# MAX17502.net
KiCad netlist of a schematic drawn in Altium Designer
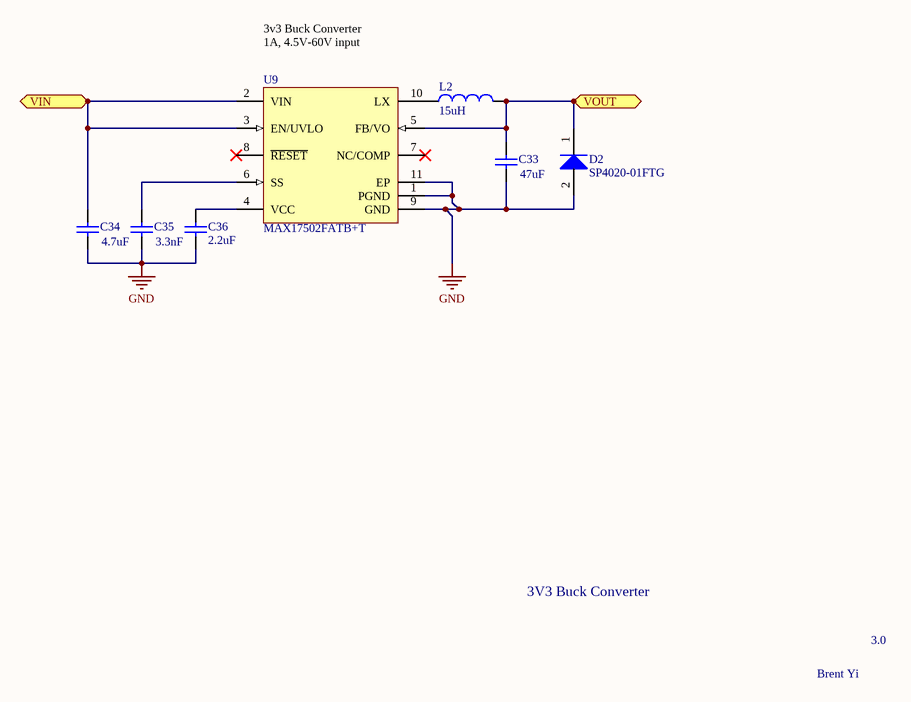
[diagram p0: MAX17502.SchDoc]

(export (version "E")
  (design (tool "Eeschema 10.0.6"))
  (components
    (comp (ref "C33")
      (value "47uF")
      (footprint "CAPC1210(3225)280_L")
      (description "CAP 100uF 10V Â±10% 1210 (3225 Metric) Thickness 2.8mm SMD")
      (fields (field (name "TOLERANCE") "Â±10%"))
      (libsource (lib "Altium Content Vault") (part "CMP-1038-02301-1"))
    )
    (comp (ref "C34")
      (value "4.7uF")
      (footprint "CAPC1210(3225)280_L")
      (description "CAP 100uF 10V Â±10% 1210 (3225 Metric) Thickness 2.8mm SMD")
      (fields (field (name "TOLERANCE") "Â±10%"))
      (libsource (lib "Altium Content Vault") (part "CMP-1038-02301-1"))
    )
    (comp (ref "C35")
      (value "3.3nF")
      (footprint "CAPC0603(1608)55_L")
      (description "CAP 2.2uF 16V Â±10% 0603 (1608 Metric) Thickness 0.55mm SMD")
      (fields (field (name "TOLERANCE") "Â±10%"))
      (libsource (lib "Altium Content Vault") (part "CMP-1035-02762-1"))
    )
    (comp (ref "C36")
      (value "2.2uF")
      (footprint "CAPC0603(1608)100_L")
      (description "CAP 1uF 6.3V Â±10% 0603 (1608 Metric) Thickness 1mm SMD")
      (fields (field (name "TOLERANCE") "Â±10%"))
      (libsource (lib "Altium Content Vault") (part "CMP-1035-02730-1"))
    )
    (comp (ref "D2")
      (value "SP4020-01FTG")
      (footprint "SOD323")
      (fields (field (name "PARTNUMBER") "MMSZ5262BT1G") (field (name "MANUFACTURER") "On Semiconductor"))
      (libsource (lib "Components") (part "SP4020-01FTG"))
    )
    (comp (ref "L2")
      (value "15uH")
      (footprint "SDR0604")
      (description "Inductor")
      (fields (field (name "Comment") "SDR0805-180ML") (field (name "PUBLISHER") "Altium Limited"))
      (libsource (lib "Components") (part "SDR0805-180ML"))
    )
    (comp (ref "U9")
      (value "MAX17502FATB+T")
      (footprint "MAXM-T1032N+1_V")
      (fields (field (name "MANUFACTURER") "Maxim"))
      (libsource (lib "Altium Content Vault") (part "MAXM-MAX17502-10"))
    )
  )
  (nets
    (net (code "1") (name "/VIN") (class "Default")
      (node (ref "C34") (pin "2") (pinfunction "2_2") (pintype "passive"))
      (node (ref "U9") (pin "2") (pinfunction "VIN_2") (pintype "power_in"))
      (node (ref "U9") (pin "3") (pinfunction "EN/UVLO_3") (pintype "input"))
    )
    (net (code "2") (name "/VOUT") (class "Default")
      (node (ref "C33") (pin "2") (pinfunction "2_2") (pintype "passive"))
      (node (ref "D2") (pin "1") (pinfunction "K_1") (pintype "passive"))
      (node (ref "L2") (pin "2") (pinfunction "2_2") (pintype "passive"))
      (node (ref "U9") (pin "5") (pinfunction "FB/VO_5") (pintype "input"))
    )
    (net (code "3") (name "GND") (class "Default")
      (node (ref "C33") (pin "1") (pinfunction "1_1") (pintype "passive"))
      (node (ref "C34") (pin "1") (pinfunction "1_1") (pintype "passive"))
      (node (ref "C35") (pin "2") (pinfunction "2_2") (pintype "passive"))
      (node (ref "C36") (pin "2") (pinfunction "2_2") (pintype "passive"))
      (node (ref "D2") (pin "2") (pinfunction "A_2") (pintype "passive"))
      (node (ref "U9") (pin "1") (pinfunction "PGND_1") (pintype "power_in"))
      (node (ref "U9") (pin "11") (pinfunction "EP_11") (pintype "power_in"))
      (node (ref "U9") (pin "9") (pinfunction "GND_9") (pintype "power_in"))
    )
    (net (code "4") (name "Net-(U9-LX)") (class "Default")
      (node (ref "L2") (pin "1") (pinfunction "1_1") (pintype "passive"))
      (node (ref "U9") (pin "10") (pinfunction "LX_10") (pintype "passive"))
    )
    (net (code "5") (name "Net-(U9-SS)") (class "Default")
      (node (ref "C35") (pin "1") (pinfunction "1_1") (pintype "passive"))
      (node (ref "U9") (pin "6") (pinfunction "SS_6") (pintype "input"))
    )
    (net (code "6") (name "Net-(U9-VCC)") (class "Default")
      (node (ref "C36") (pin "1") (pinfunction "1_1") (pintype "passive"))
      (node (ref "U9") (pin "4") (pinfunction "VCC_4") (pintype "power_in"))
    )
    (net (code "7") (name "unconnected-(U9-NC{slash}COMP-Pad7)") (class "Default")
      (node (ref "U9") (pin "7") (pinfunction "NC/COMP_7") (pintype "passive+no_connect"))
    )
    (net (code "8") (name "unconnected-(U9-~{RESET}-Pad8)") (class "Default")
      (node (ref "U9") (pin "8") (pinfunction "~{RESET}_8") (pintype "open_collector+no_connect"))
    )
  )
)
